# Pulse_heart.net
KiCad netlist of a schematic drawn in EasyEDA
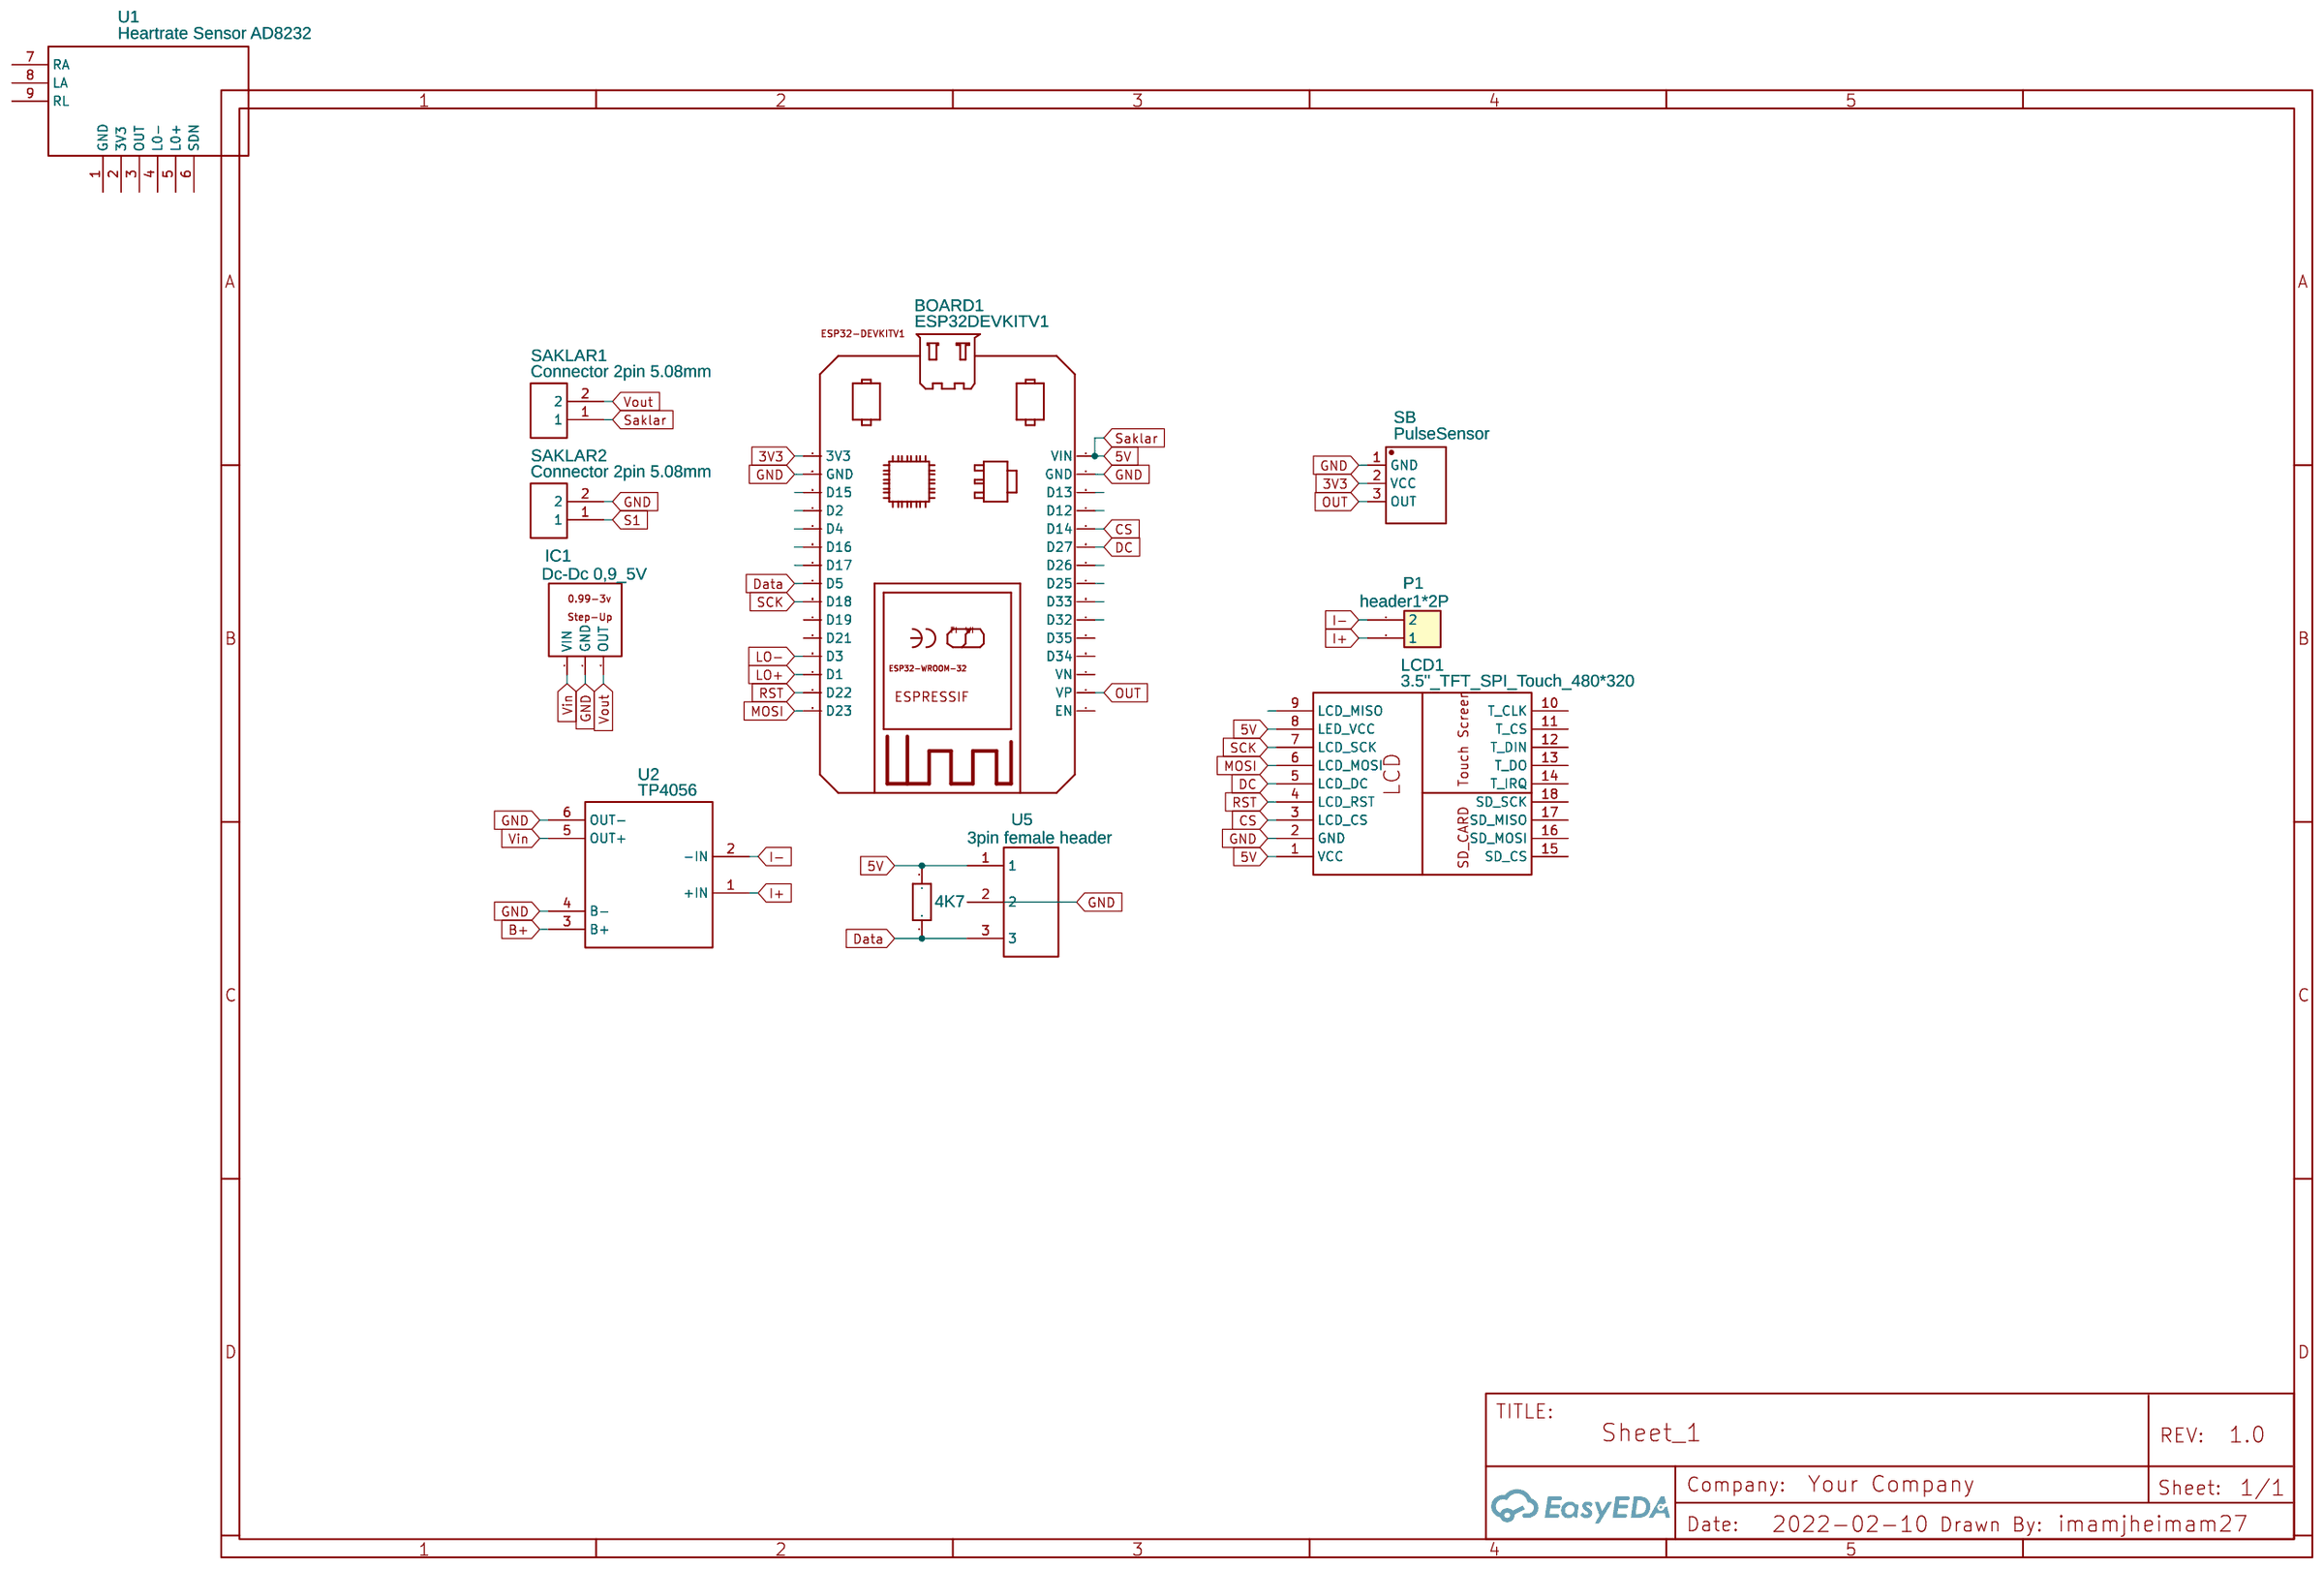
[diagram p0: schematic sheet]

(export (version "E")
  (design (tool "Eeschema 10.0.6"))
  (components
    (comp (ref "4K7") (value ".") (libsource (lib "") (part "NFR25H0002208J")))
    (comp (ref "BOARD1") (value "ESP32DEVKITV1") (libsource (lib "") (part "ESP32DEVKITV1")))
    (comp (ref "IC1") (value "Dc-Dc 0,9_5V") (libsource (lib "") (part "Dc-Dc 0,9_5V")))
    (comp (ref "LCD1")
      (value "3.5\"_TFT_SPI_Touch_480*320")
      (fields (field (name "BOM_Manufacturer Part") "ILI 9488"))
      (libsource (lib "") (part "3.5&quot;_TFT_SPI_Touch_480*320"))
    )
    (comp (ref "P1") (value "header1*2P") (libsource (lib "") (part "header1*2P")))
    (comp (ref "SAKLAR1") (value "Connector 2pin 5.08mm") (libsource (lib "") (part "Connector 2pin 5.08mm")))
    (comp (ref "SAKLAR2") (value "Connector 2pin 5.08mm") (libsource (lib "") (part "Connector 2pin 5.08mm")))
    (comp (ref "SB") (value "PulseSensor") (libsource (lib "") (part "PulseSensor")))
    (comp (ref "U1") (value "Heartrate Sensor AD8232") (libsource (lib "") (part "Heartrate Sensor AD8232")))
    (comp (ref "U2") (value "TP4056") (libsource (lib "") (part "TP4056")))
    (comp (ref "U5") (value "3pin female header") (libsource (lib "") (part "3pin female header")))
  )
  (nets
    (net (code "1") (name "3V3") (class "Default")
      (node (ref "BOARD1") (pin "3V3") (pinfunction "3V3_3V3") (pintype "bidirectional"))
      (node (ref "SB") (pin "2") (pinfunction "VCC_2") (pintype "input"))
    )
    (net (code "2") (name "5V") (class "Default")
      (node (ref "4K7") (pin "1") (pinfunction "1_1") (pintype "bidirectional"))
      (node (ref "BOARD1") (pin "VIN") (pinfunction "VIN_VIN") (pintype "bidirectional"))
      (node (ref "LCD1") (pin "1") (pinfunction "VCC_1") (pintype "unspecified"))
      (node (ref "LCD1") (pin "8") (pinfunction "LED_VCC_8") (pintype "unspecified"))
      (node (ref "SAKLAR1") (pin "1") (pinfunction "1_1") (pintype "unspecified"))
      (node (ref "U5") (pin "1") (pinfunction "1_1") (pintype "unspecified"))
    )
    (net (code "3") (name "B+") (class "Default")
      (node (ref "U2") (pin "3") (pinfunction "B+_3") (pintype "unspecified"))
    )
    (net (code "4") (name "CS") (class "Default")
      (node (ref "BOARD1") (pin "D14") (pinfunction "D14_D14") (pintype "bidirectional"))
      (node (ref "LCD1") (pin "3") (pinfunction "LCD_CS_3") (pintype "unspecified"))
    )
    (net (code "5") (name "DC") (class "Default")
      (node (ref "BOARD1") (pin "D27") (pinfunction "D27_D27") (pintype "bidirectional"))
      (node (ref "LCD1") (pin "5") (pinfunction "LCD_DC_5") (pintype "unspecified"))
    )
    (net (code "6") (name "Data") (class "Default")
      (node (ref "4K7") (pin "2") (pinfunction "2_2") (pintype "bidirectional"))
      (node (ref "BOARD1") (pin "D5") (pinfunction "D5_D5") (pintype "bidirectional"))
      (node (ref "U5") (pin "3") (pinfunction "3_3") (pintype "unspecified"))
    )
    (net (code "7") (name "GND") (class "Default")
      (node (ref "BOARD1") (pin "GND") (pinfunction "GND_GND") (pintype "bidirectional"))
      (node (ref "BOARD1") (pin "GND@1") (pinfunction "GND_GND@1") (pintype "bidirectional"))
      (node (ref "IC1") (pin "2") (pinfunction "GND_2") (pintype "unspecified"))
      (node (ref "LCD1") (pin "2") (pinfunction "GND_2") (pintype "unspecified"))
      (node (ref "SAKLAR2") (pin "2") (pinfunction "2_2") (pintype "unspecified"))
      (node (ref "SB") (pin "1") (pinfunction "GND_1") (pintype "input"))
      (node (ref "U2") (pin "4") (pinfunction "B-_4") (pintype "unspecified"))
      (node (ref "U2") (pin "6") (pinfunction "OUT-_6") (pintype "unspecified"))
      (node (ref "U5") (pin "2") (pinfunction "2_2") (pintype "unspecified"))
    )
    (net (code "8") (name "I+") (class "Default")
      (node (ref "P1") (pin "1") (pinfunction "1_1") (pintype "input"))
      (node (ref "U2") (pin "1") (pinfunction "+IN_1") (pintype "unspecified"))
    )
    (net (code "9") (name "I-") (class "Default")
      (node (ref "P1") (pin "2") (pinfunction "2_2") (pintype "input"))
      (node (ref "U2") (pin "2") (pinfunction "-IN_2") (pintype "unspecified"))
    )
    (net (code "10") (name "LO+") (class "Default")
      (node (ref "BOARD1") (pin "D1") (pinfunction "D1_D1") (pintype "bidirectional"))
    )
    (net (code "11") (name "LO-") (class "Default")
      (node (ref "BOARD1") (pin "D3") (pinfunction "D3_D3") (pintype "bidirectional"))
    )
    (net (code "12") (name "MOSI") (class "Default")
      (node (ref "BOARD1") (pin "D23") (pinfunction "D23_D23") (pintype "bidirectional"))
      (node (ref "LCD1") (pin "6") (pinfunction "LCD_MOSI_6") (pintype "unspecified"))
    )
    (net (code "13") (name "OUT") (class "Default")
      (node (ref "BOARD1") (pin "VP") (pinfunction "VP_VP") (pintype "bidirectional"))
      (node (ref "SB") (pin "3") (pinfunction "OUT_3") (pintype "output"))
    )
    (net (code "14") (name "RST") (class "Default")
      (node (ref "BOARD1") (pin "D22") (pinfunction "D22_D22") (pintype "bidirectional"))
      (node (ref "LCD1") (pin "4") (pinfunction "LCD_RST_4") (pintype "unspecified"))
    )
    (net (code "15") (name "S1") (class "Default")
      (node (ref "SAKLAR2") (pin "1") (pinfunction "1_1") (pintype "unspecified"))
    )
    (net (code "16") (name "SCK") (class "Default")
      (node (ref "BOARD1") (pin "D18") (pinfunction "D18_D18") (pintype "bidirectional"))
      (node (ref "LCD1") (pin "7") (pinfunction "LCD_SCK_7") (pintype "unspecified"))
    )
    (net (code "17") (name "Vin") (class "Default")
      (node (ref "IC1") (pin "1") (pinfunction "VIN_1") (pintype "unspecified"))
      (node (ref "U2") (pin "5") (pinfunction "OUT+_5") (pintype "unspecified"))
    )
    (net (code "18") (name "Vout") (class "Default")
      (node (ref "IC1") (pin "3") (pinfunction "OUT_3") (pintype "unspecified"))
      (node (ref "SAKLAR1") (pin "2") (pinfunction "2_2") (pintype "unspecified"))
    )
    (net (code "19") (name "unconnected-(BOARD1-PadD2)") (class "Default")
      (node (ref "BOARD1") (pin "D2") (pinfunction "D2_D2") (pintype "bidirectional"))
    )
    (net (code "20") (name "unconnected-(BOARD1-PadD4)") (class "Default")
      (node (ref "BOARD1") (pin "D4") (pinfunction "D4_D4") (pintype "bidirectional"))
    )
    (net (code "21") (name "unconnected-(BOARD1-PadD12)") (class "Default")
      (node (ref "BOARD1") (pin "D12") (pinfunction "D12_D12") (pintype "bidirectional"))
    )
    (net (code "22") (name "unconnected-(BOARD1-PadD13)") (class "Default")
      (node (ref "BOARD1") (pin "D13") (pinfunction "D13_D13") (pintype "bidirectional"))
    )
    (net (code "23") (name "unconnected-(BOARD1-PadD15)") (class "Default")
      (node (ref "BOARD1") (pin "D15") (pinfunction "D15_D15") (pintype "bidirectional"))
    )
    (net (code "24") (name "unconnected-(BOARD1-PadD16)") (class "Default")
      (node (ref "BOARD1") (pin "D16") (pinfunction "D16_D16") (pintype "bidirectional"))
    )
    (net (code "25") (name "unconnected-(BOARD1-PadD17)") (class "Default")
      (node (ref "BOARD1") (pin "D17") (pinfunction "D17_D17") (pintype "bidirectional"))
    )
    (net (code "26") (name "unconnected-(BOARD1-PadD19)") (class "Default")
      (node (ref "BOARD1") (pin "D19") (pinfunction "D19_D19") (pintype "bidirectional"))
    )
    (net (code "27") (name "unconnected-(BOARD1-PadD21)") (class "Default")
      (node (ref "BOARD1") (pin "D21") (pinfunction "D21_D21") (pintype "bidirectional"))
    )
    (net (code "28") (name "unconnected-(BOARD1-PadD25)") (class "Default")
      (node (ref "BOARD1") (pin "D25") (pinfunction "D25_D25") (pintype "bidirectional"))
    )
    (net (code "29") (name "unconnected-(BOARD1-PadD26)") (class "Default")
      (node (ref "BOARD1") (pin "D26") (pinfunction "D26_D26") (pintype "bidirectional"))
    )
    (net (code "30") (name "unconnected-(BOARD1-PadD32)") (class "Default")
      (node (ref "BOARD1") (pin "D32") (pinfunction "D32_D32") (pintype "bidirectional"))
    )
    (net (code "31") (name "unconnected-(BOARD1-PadD33)") (class "Default")
      (node (ref "BOARD1") (pin "D33") (pinfunction "D33_D33") (pintype "bidirectional"))
    )
    (net (code "32") (name "unconnected-(BOARD1-PadD34)") (class "Default")
      (node (ref "BOARD1") (pin "D34") (pinfunction "D34_D34") (pintype "bidirectional"))
    )
    (net (code "33") (name "unconnected-(BOARD1-PadD35)") (class "Default")
      (node (ref "BOARD1") (pin "D35") (pinfunction "D35_D35") (pintype "bidirectional"))
    )
    (net (code "34") (name "unconnected-(BOARD1-PadEN)") (class "Default")
      (node (ref "BOARD1") (pin "EN") (pinfunction "EN_EN") (pintype "bidirectional"))
    )
    (net (code "35") (name "unconnected-(BOARD1-PadVN)") (class "Default")
      (node (ref "BOARD1") (pin "VN") (pinfunction "VN_VN") (pintype "bidirectional"))
    )
    (net (code "36") (name "unconnected-(LCD1-LCD_MISO-Pad9)") (class "Default")
      (node (ref "LCD1") (pin "9") (pinfunction "LCD_MISO_9") (pintype "unspecified"))
    )
    (net (code "37") (name "unconnected-(LCD1-SD_CS-Pad15)") (class "Default")
      (node (ref "LCD1") (pin "15") (pinfunction "SD_CS_15") (pintype "unspecified"))
    )
    (net (code "38") (name "unconnected-(LCD1-SD_MISO-Pad17)") (class "Default")
      (node (ref "LCD1") (pin "17") (pinfunction "SD_MISO_17") (pintype "unspecified"))
    )
    (net (code "39") (name "unconnected-(LCD1-SD_MOSI-Pad16)") (class "Default")
      (node (ref "LCD1") (pin "16") (pinfunction "SD_MOSI_16") (pintype "unspecified"))
    )
    (net (code "40") (name "unconnected-(LCD1-SD_SCK-Pad18)") (class "Default")
      (node (ref "LCD1") (pin "18") (pinfunction "SD_SCK_18") (pintype "unspecified"))
    )
    (net (code "41") (name "unconnected-(LCD1-T_CLK-Pad10)") (class "Default")
      (node (ref "LCD1") (pin "10") (pinfunction "T_CLK_10") (pintype "unspecified"))
    )
    (net (code "42") (name "unconnected-(LCD1-T_CS-Pad11)") (class "Default")
      (node (ref "LCD1") (pin "11") (pinfunction "T_CS_11") (pintype "unspecified"))
    )
    (net (code "43") (name "unconnected-(LCD1-T_DIN-Pad12)") (class "Default")
      (node (ref "LCD1") (pin "12") (pinfunction "T_DIN_12") (pintype "unspecified"))
    )
    (net (code "44") (name "unconnected-(LCD1-T_DO-Pad13)") (class "Default")
      (node (ref "LCD1") (pin "13") (pinfunction "T_DO_13") (pintype "unspecified"))
    )
    (net (code "45") (name "unconnected-(LCD1-T_IRQ-Pad14)") (class "Default")
      (node (ref "LCD1") (pin "14") (pinfunction "T_IRQ_14") (pintype "unspecified"))
    )
    (net (code "46") (name "unconnected-(U1-3V3-Pad2)") (class "Default")
      (node (ref "U1") (pin "2") (pinfunction "3V3_2") (pintype "unspecified"))
    )
    (net (code "47") (name "unconnected-(U1-GND-Pad1)") (class "Default")
      (node (ref "U1") (pin "1") (pinfunction "GND_1") (pintype "unspecified"))
    )
    (net (code "48") (name "unconnected-(U1-L0+-Pad5)") (class "Default")
      (node (ref "U1") (pin "5") (pinfunction "L0+_5") (pintype "unspecified"))
    )
    (net (code "49") (name "unconnected-(U1-L0--Pad4)") (class "Default")
      (node (ref "U1") (pin "4") (pinfunction "L0-_4") (pintype "unspecified"))
    )
    (net (code "50") (name "unconnected-(U1-LA-Pad8)") (class "Default")
      (node (ref "U1") (pin "8") (pinfunction "LA_8") (pintype "unspecified"))
    )
    (net (code "51") (name "unconnected-(U1-OUT-Pad3)") (class "Default")
      (node (ref "U1") (pin "3") (pinfunction "OUT_3") (pintype "unspecified"))
    )
    (net (code "52") (name "unconnected-(U1-RA-Pad7)") (class "Default")
      (node (ref "U1") (pin "7") (pinfunction "RA_7") (pintype "unspecified"))
    )
    (net (code "53") (name "unconnected-(U1-RL-Pad9)") (class "Default")
      (node (ref "U1") (pin "9") (pinfunction "RL_9") (pintype "unspecified"))
    )
    (net (code "54") (name "unconnected-(U1-SDN-Pad6)") (class "Default")
      (node (ref "U1") (pin "6") (pinfunction "SDN_6") (pintype "unspecified"))
    )
  )
)
